# Klasmata.net
KiCad netlist of a schematic drawn in EAGLE
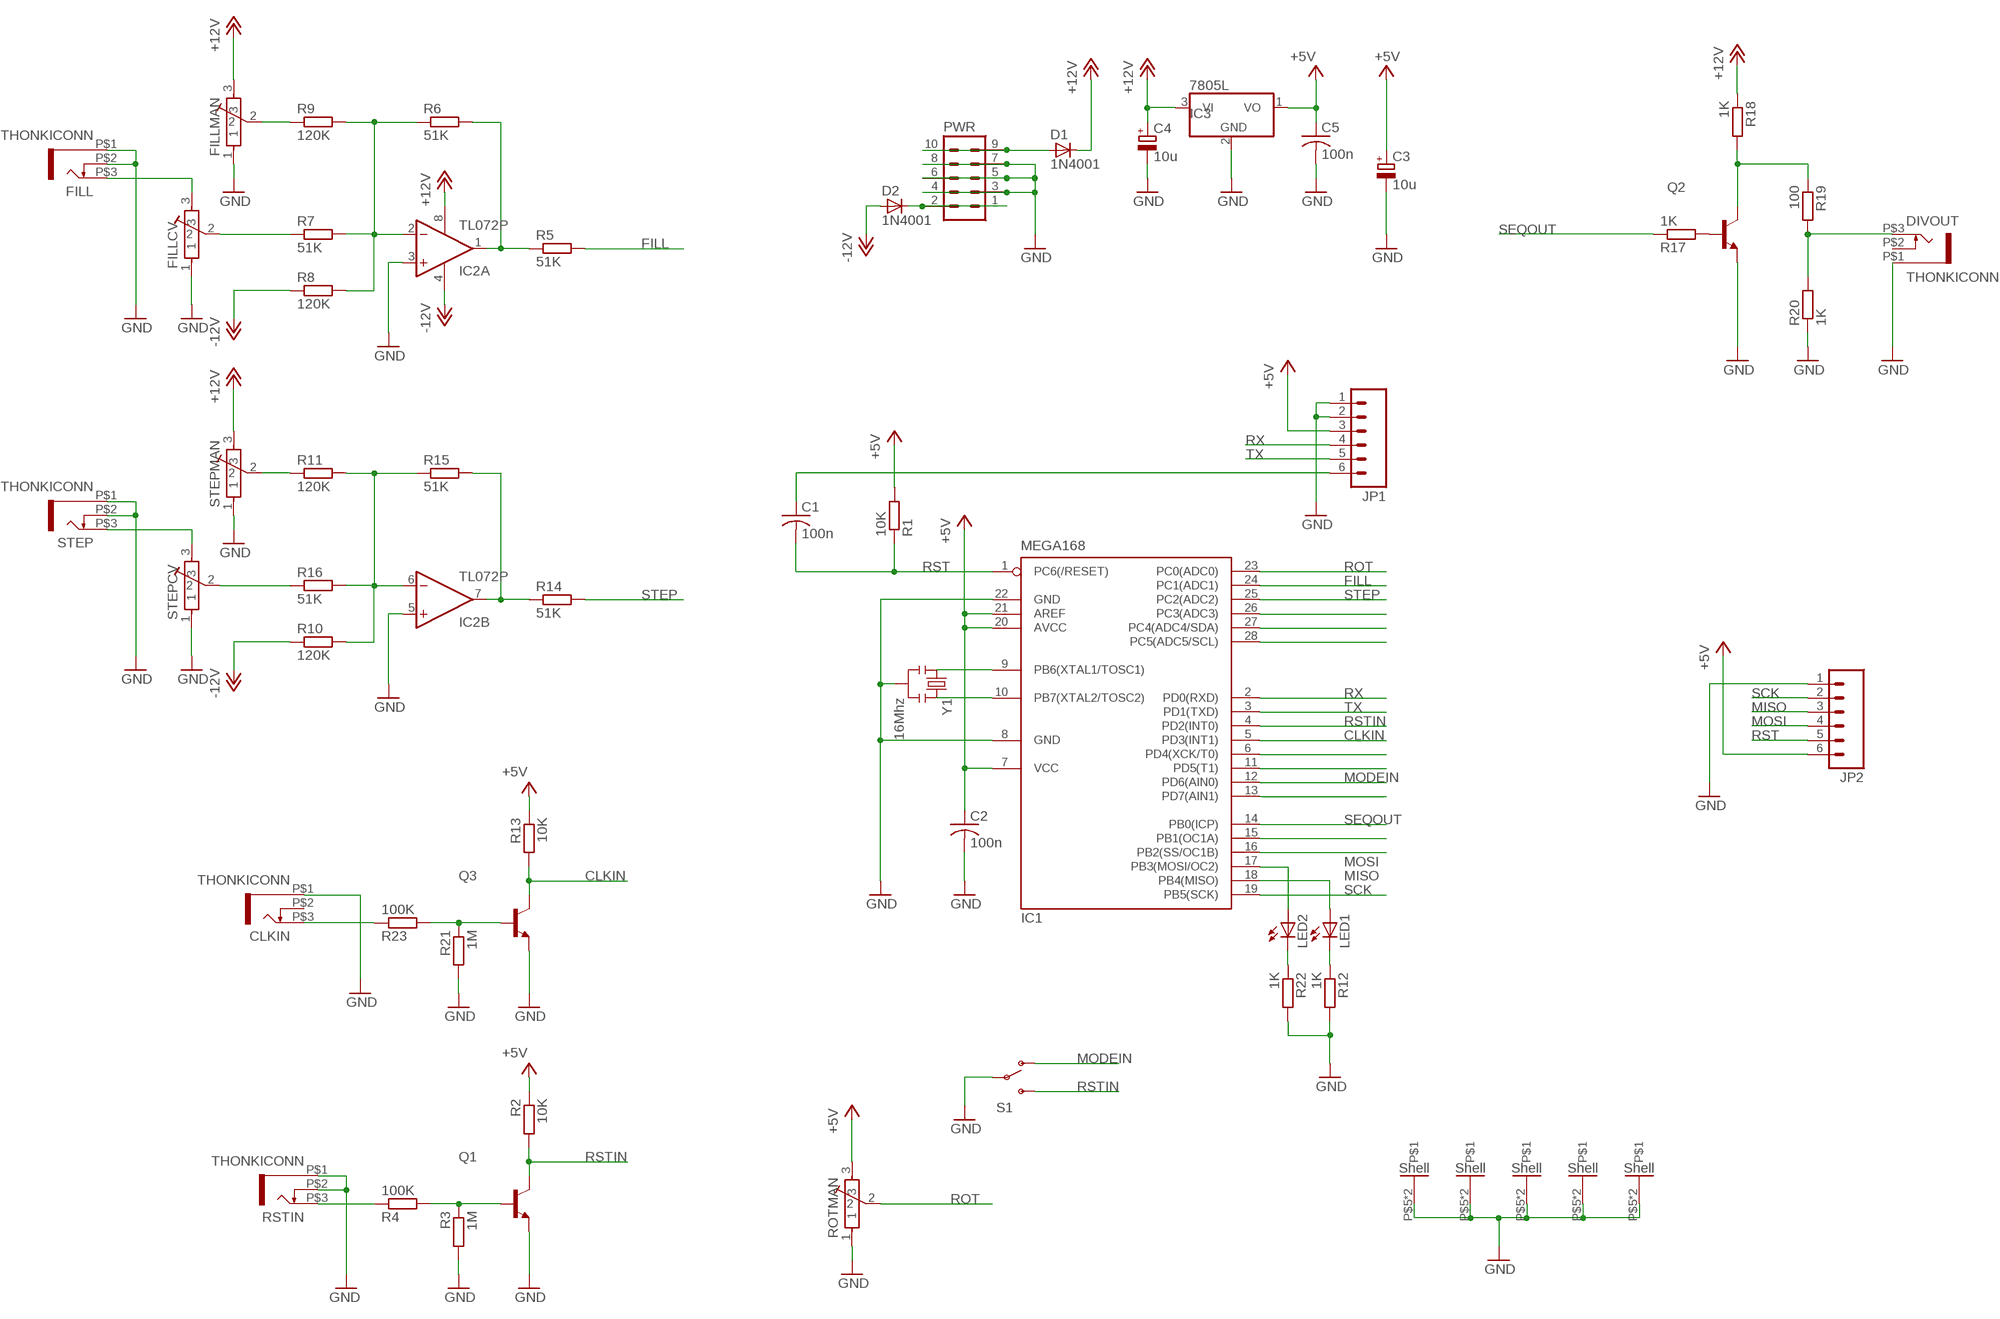
[diagram p0: schematic, sheet 1]

(export (version "E")
  (design (tool "Eeschema 10.0.6"))
  (components
    (comp (ref "C1")
      (value "100n")
      (footprint "eagle-import:C050-024X044")
      (libsource (lib "eagle-import") (part "C-US050-024X044"))
    )
    (comp (ref "C2")
      (value "100n")
      (footprint "eagle-import:C050-024X044")
      (libsource (lib "eagle-import") (part "C-US050-024X044"))
    )
    (comp (ref "C3")
      (value "10u")
      (footprint "eagle-import:E2,5-6")
      (libsource (lib "eagle-import") (part "resistor_CPOL-EUE2.5-6"))
    )
    (comp (ref "C4")
      (value "10u")
      (footprint "eagle-import:E5-6")
      (libsource (lib "eagle-import") (part "CPOL-EUE5-6"))
    )
    (comp (ref "C5")
      (value "100n")
      (footprint "eagle-import:C050-024X044")
      (libsource (lib "eagle-import") (part "C-US050-024X044"))
    )
    (comp (ref "CLKIN")
      (value "THONKICONN")
      (footprint "eagle-import:THONKICONN")
      (libsource (lib "eagle-import") (part "THONKICONN"))
    )
    (comp (ref "D1")
      (value "1N4001")
      (footprint "eagle-import:DIODE-1N4001")
      (libsource (lib "eagle-import") (part "DIODE1N4001"))
    )
    (comp (ref "D2")
      (value "1N4001")
      (footprint "eagle-import:DIODE-1N4001")
      (libsource (lib "eagle-import") (part "DIODE1N4001"))
    )
    (comp (ref "DIVOUT")
      (value "THONKICONN")
      (footprint "eagle-import:THONKICONN")
      (libsource (lib "eagle-import") (part "THONKICONN"))
    )
    (comp (ref "FILL")
      (value "THONKICONN")
      (footprint "eagle-import:THONKICONN")
      (libsource (lib "eagle-import") (part "THONKICONN"))
    )
    (comp (ref "FILLCV")
      (value "POT-ALPS-RK09L1140")
      (footprint "eagle-import:POT-ALPS-RK09L1140")
      (libsource (lib "eagle-import") (part "POT-ALPS-RK09L1140"))
    )
    (comp (ref "FILLMAN")
      (value "POT-ALPS-RK09L1140")
      (footprint "eagle-import:POT-ALPS-RK09L1140")
      (libsource (lib "eagle-import") (part "POT-ALPS-RK09L1140"))
    )
    (comp (ref "IC1")
      (value "MEGA168")
      (footprint "eagle-import:DIL28-3")
      (libsource (lib "eagle-import") (part "MEGA8-P"))
    )
    (comp (ref "IC2")
      (value "TL072P")
      (footprint "eagle-import:DIL08")
      (libsource (lib "eagle-import") (part "TL072P"))
    )
    (comp (ref "IC3")
      (value "7805L")
      (footprint "eagle-import:TO92")
      (libsource (lib "eagle-import") (part "78L05"))
    )
    (comp (ref "JP1")
      (value "M06SIP")
      (footprint "eagle-import:1X06")
      (libsource (lib "eagle-import") (part "M06SIP"))
    )
    (comp (ref "JP2")
      (value "M06SIP")
      (footprint "eagle-import:1X06")
      (libsource (lib "eagle-import") (part "M06SIP"))
    )
    (comp (ref "LED1")
      (value "LED3MM")
      (footprint "eagle-import:LED3MM")
      (libsource (lib "eagle-import") (part "LED3MM"))
    )
    (comp (ref "LED2")
      (value "LED3MM")
      (footprint "eagle-import:LED3MM")
      (libsource (lib "eagle-import") (part "LED3MM"))
    )
    (comp (ref "PWR")
      (value "MA05-2")
      (footprint "eagle-import:MA05-2")
      (libsource (lib "eagle-import") (part "MA05-2"))
    )
    (comp (ref "Q1")
      (value "2N3904-NPN-TO92-EBC")
      (footprint "eagle-import:TO92-EBC")
      (libsource (lib "eagle-import") (part "-NPN-TO92-EBC2N3904"))
    )
    (comp (ref "Q2")
      (value "2N3904-NPN-TO92-EBC")
      (footprint "eagle-import:TO92-EBC")
      (libsource (lib "eagle-import") (part "-NPN-TO92-EBC2N3904"))
    )
    (comp (ref "Q3")
      (value "2N3904-NPN-TO92-EBC")
      (footprint "eagle-import:TO92-EBC")
      (libsource (lib "eagle-import") (part "-NPN-TO92-EBC2N3904"))
    )
    (comp (ref "R1")
      (value "10K")
      (footprint "eagle-import:0204_7")
      (libsource (lib "eagle-import") (part "R-EU_0204/7"))
    )
    (comp (ref "R2")
      (value "10K")
      (footprint "eagle-import:0204_7")
      (libsource (lib "eagle-import") (part "R-EU_0204/7"))
    )
    (comp (ref "R3")
      (value "1M")
      (footprint "eagle-import:0204_7")
      (libsource (lib "eagle-import") (part "R-EU_0204/7"))
    )
    (comp (ref "R4")
      (value "100K")
      (footprint "eagle-import:0204_7")
      (libsource (lib "eagle-import") (part "R-EU_0204/7"))
    )
    (comp (ref "R5")
      (value "51K")
      (footprint "eagle-import:0204_7")
      (libsource (lib "eagle-import") (part "R-EU_0204/7"))
    )
    (comp (ref "R6")
      (value "51K")
      (footprint "eagle-import:0204_7")
      (libsource (lib "eagle-import") (part "R-EU_0204/7"))
    )
    (comp (ref "R7")
      (value "51K")
      (footprint "eagle-import:0204_7")
      (libsource (lib "eagle-import") (part "R-EU_0204/7"))
    )
    (comp (ref "R8")
      (value "120K")
      (footprint "eagle-import:0204_7")
      (libsource (lib "eagle-import") (part "R-EU_0204/7"))
    )
    (comp (ref "R9")
      (value "120K")
      (footprint "eagle-import:0204_7")
      (libsource (lib "eagle-import") (part "R-EU_0204/7"))
    )
    (comp (ref "R10")
      (value "120K")
      (footprint "eagle-import:0204_7")
      (libsource (lib "eagle-import") (part "R-EU_0204/7"))
    )
    (comp (ref "R11")
      (value "120K")
      (footprint "eagle-import:0204_7")
      (libsource (lib "eagle-import") (part "R-EU_0204/7"))
    )
    (comp (ref "R12")
      (value "1K")
      (footprint "eagle-import:0204_7")
      (libsource (lib "eagle-import") (part "R-EU_0204/7"))
    )
    (comp (ref "R13")
      (value "10K")
      (footprint "eagle-import:0204_7")
      (libsource (lib "eagle-import") (part "R-EU_0204/7"))
    )
    (comp (ref "R14")
      (value "51K")
      (footprint "eagle-import:0204_7")
      (libsource (lib "eagle-import") (part "R-EU_0204/7"))
    )
    (comp (ref "R15")
      (value "51K")
      (footprint "eagle-import:0204_7")
      (libsource (lib "eagle-import") (part "R-EU_0204/7"))
    )
    (comp (ref "R16")
      (value "51K")
      (footprint "eagle-import:0204_7")
      (libsource (lib "eagle-import") (part "R-EU_0204/7"))
    )
    (comp (ref "R17")
      (value "1K")
      (footprint "eagle-import:0204_7")
      (libsource (lib "eagle-import") (part "R-EU_0204/7"))
    )
    (comp (ref "R18")
      (value "1K")
      (footprint "eagle-import:0204_7")
      (libsource (lib "eagle-import") (part "R-EU_0204/7"))
    )
    (comp (ref "R19")
      (value "100")
      (footprint "eagle-import:0204_7")
      (libsource (lib "eagle-import") (part "R-EU_0204/7"))
    )
    (comp (ref "R20")
      (value "1K")
      (footprint "eagle-import:0204_7")
      (libsource (lib "eagle-import") (part "R-EU_0204/7"))
    )
    (comp (ref "R21")
      (value "1M")
      (footprint "eagle-import:0204_7")
      (libsource (lib "eagle-import") (part "R-EU_0204/7"))
    )
    (comp (ref "R22")
      (value "1K")
      (footprint "eagle-import:0204_7")
      (libsource (lib "eagle-import") (part "R-EU_0204/7"))
    )
    (comp (ref "R23")
      (value "100K")
      (footprint "eagle-import:0204_7")
      (libsource (lib "eagle-import") (part "R-EU_0204/7"))
    )
    (comp (ref "ROTMAN")
      (value "POT-ALPS-RK09L1140")
      (footprint "eagle-import:POT-ALPS-RK09L1140")
      (libsource (lib "eagle-import") (part "POT-ALPS-RK09L1140"))
    )
    (comp (ref "RSTIN")
      (value "THONKICONN")
      (footprint "eagle-import:THONKICONN")
      (libsource (lib "eagle-import") (part "THONKICONN"))
    )
    (comp (ref "S1")
      (value "SWITCH-SPST")
      (footprint "eagle-import:SWITCH-SPDT-SALECOM-T8014")
      (libsource (lib "eagle-import") (part "SWITCH-SPST"))
    )
    (comp (ref "STEP")
      (value "THONKICONN")
      (footprint "eagle-import:THONKICONN")
      (libsource (lib "eagle-import") (part "THONKICONN"))
    )
    (comp (ref "STEPCV")
      (value "POT-ALPS-RK09L1140")
      (footprint "eagle-import:POT-ALPS-RK09L1140")
      (libsource (lib "eagle-import") (part "POT-ALPS-RK09L1140"))
    )
    (comp (ref "STEPMAN")
      (value "POT-ALPS-RK09L1140")
      (footprint "eagle-import:POT-ALPS-RK09L1140")
      (libsource (lib "eagle-import") (part "POT-ALPS-RK09L1140"))
    )
    (comp (ref "Y1")
      (value "16Mhz")
      (footprint "eagle-import:RESONATOR-PTH")
      (libsource (lib "eagle-import") (part "RESONATORPTH"))
    )
  )
  (nets
    (net (code "1") (name "+5V") (class "Default")
      (node (ref "C2") (pin "1") (pinfunction "1_1") (pintype "passive"))
      (node (ref "C3") (pin "+") (pinfunction "+_+") (pintype "passive"))
      (node (ref "C5") (pin "1") (pinfunction "1_1") (pintype "passive"))
      (node (ref "IC1") (pin "20") (pinfunction "AVCC_20") (pintype "power_in"))
      (node (ref "IC1") (pin "21") (pinfunction "AREF_21") (pintype "passive"))
      (node (ref "IC1") (pin "7") (pinfunction "VCC_7") (pintype "power_in"))
      (node (ref "IC3") (pin "1") (pinfunction "VO_1") (pintype "passive"))
      (node (ref "JP1") (pin "3") (pinfunction "3_3") (pintype "passive"))
      (node (ref "JP2") (pin "6") (pinfunction "6_6") (pintype "passive"))
      (node (ref "R1") (pin "2") (pinfunction "2_2") (pintype "passive"))
      (node (ref "R13") (pin "1") (pinfunction "1_1") (pintype "passive"))
      (node (ref "R2") (pin "1") (pinfunction "1_1") (pintype "passive"))
      (node (ref "ROTMAN") (pin "3") (pinfunction "3_3") (pintype "bidirectional"))
    )
    (net (code "2") (name "+12V") (class "Default")
      (node (ref "C4") (pin "+") (pinfunction "+_+") (pintype "passive"))
      (node (ref "D1") (pin "C") (pinfunction "C_C") (pintype "passive"))
      (node (ref "FILLMAN") (pin "3") (pinfunction "3_3") (pintype "bidirectional"))
      (node (ref "IC2") (pin "8") (pinfunction "V+_8") (pintype "power_in"))
      (node (ref "IC3") (pin "3") (pinfunction "VI_3") (pintype "input"))
      (node (ref "R18") (pin "1") (pinfunction "1_1") (pintype "passive"))
      (node (ref "STEPMAN") (pin "3") (pinfunction "3_3") (pintype "bidirectional"))
    )
    (net (code "3") (name "-12V") (class "Default")
      (node (ref "D2") (pin "A") (pinfunction "A_A") (pintype "passive"))
      (node (ref "IC2") (pin "4") (pinfunction "V-_4") (pintype "power_in"))
      (node (ref "R10") (pin "1") (pinfunction "1_1") (pintype "passive"))
      (node (ref "R8") (pin "1") (pinfunction "1_1") (pintype "passive"))
    )
    (net (code "4") (name "/CLKIN") (class "Default")
      (node (ref "IC1") (pin "5") (pinfunction "PD3(INT1)_5") (pintype "bidirectional"))
      (node (ref "Q3") (pin "C") (pinfunction "C_C") (pintype "passive"))
      (node (ref "R13") (pin "2") (pinfunction "2_2") (pintype "passive"))
    )
    (net (code "5") (name "/FILL") (class "Default")
      (node (ref "IC1") (pin "24") (pinfunction "PC1(ADC1)_24") (pintype "bidirectional"))
      (node (ref "R5") (pin "2") (pinfunction "2_2") (pintype "passive"))
    )
    (net (code "6") (name "/MISO") (class "Default")
      (node (ref "IC1") (pin "18") (pinfunction "PB4(MISO)_18") (pintype "bidirectional"))
      (node (ref "JP2") (pin "3") (pinfunction "3_3") (pintype "passive"))
      (node (ref "LED1") (pin "A") (pinfunction "A_A") (pintype "passive"))
    )
    (net (code "7") (name "/MODEIN") (class "Default")
      (node (ref "IC1") (pin "12") (pinfunction "PD6(AIN0)_12") (pintype "bidirectional"))
      (node (ref "S1") (pin "1") (pinfunction "O_1") (pintype "passive"))
    )
    (net (code "8") (name "/MOSI") (class "Default")
      (node (ref "IC1") (pin "17") (pinfunction "PB3(MOSI/OC2)_17") (pintype "bidirectional"))
      (node (ref "JP2") (pin "4") (pinfunction "4_4") (pintype "passive"))
      (node (ref "LED2") (pin "A") (pinfunction "A_A") (pintype "passive"))
    )
    (net (code "9") (name "/ROT") (class "Default")
      (node (ref "IC1") (pin "23") (pinfunction "PC0(ADC0)_23") (pintype "bidirectional"))
      (node (ref "ROTMAN") (pin "2") (pinfunction "2_2") (pintype "bidirectional"))
    )
    (net (code "10") (name "/RST") (class "Default")
      (node (ref "C1") (pin "2") (pinfunction "2_2") (pintype "passive"))
      (node (ref "IC1") (pin "1") (pinfunction "PC6(/RESET)_1") (pintype "bidirectional"))
      (node (ref "JP2") (pin "5") (pinfunction "5_5") (pintype "passive"))
      (node (ref "R1") (pin "1") (pinfunction "1_1") (pintype "passive"))
    )
    (net (code "11") (name "/RSTIN") (class "Default")
      (node (ref "IC1") (pin "4") (pinfunction "PD2(INT0)_4") (pintype "bidirectional"))
      (node (ref "Q1") (pin "C") (pinfunction "C_C") (pintype "passive"))
      (node (ref "R2") (pin "2") (pinfunction "2_2") (pintype "passive"))
      (node (ref "S1") (pin "3") (pinfunction "S_3") (pintype "passive"))
    )
    (net (code "12") (name "/RX") (class "Default")
      (node (ref "IC1") (pin "2") (pinfunction "PD0(RXD)_2") (pintype "bidirectional"))
      (node (ref "JP1") (pin "4") (pinfunction "4_4") (pintype "passive"))
    )
    (net (code "13") (name "/SCK") (class "Default")
      (node (ref "IC1") (pin "19") (pinfunction "PB5(SCK)_19") (pintype "bidirectional"))
      (node (ref "JP2") (pin "2") (pinfunction "2_2") (pintype "passive"))
    )
    (net (code "14") (name "/SEQOUT") (class "Default")
      (node (ref "IC1") (pin "14") (pinfunction "PB0(ICP)_14") (pintype "bidirectional"))
      (node (ref "R17") (pin "1") (pinfunction "1_1") (pintype "passive"))
    )
    (net (code "15") (name "/STEP") (class "Default")
      (node (ref "IC1") (pin "25") (pinfunction "PC2(ADC2)_25") (pintype "bidirectional"))
      (node (ref "R14") (pin "2") (pinfunction "2_2") (pintype "passive"))
    )
    (net (code "16") (name "/TX") (class "Default")
      (node (ref "IC1") (pin "3") (pinfunction "PD1(TXD)_3") (pintype "bidirectional"))
      (node (ref "JP1") (pin "5") (pinfunction "5_5") (pintype "passive"))
    )
    (net (code "17") (name "GND") (class "Default")
      (node (ref "C2") (pin "2") (pinfunction "2_2") (pintype "passive"))
      (node (ref "C3") (pin "-") (pinfunction "-_-") (pintype "passive"))
      (node (ref "C4") (pin "-") (pinfunction "-_-") (pintype "passive"))
      (node (ref "C5") (pin "2") (pinfunction "2_2") (pintype "passive"))
      (node (ref "CLKIN") (pin "P$1") (pinfunction "5_P$1") (pintype "passive"))
      (node (ref "DIVOUT") (pin "P$1") (pinfunction "5_P$1") (pintype "passive"))
      (node (ref "FILL") (pin "P$1") (pinfunction "5_P$1") (pintype "passive"))
      (node (ref "FILL") (pin "P$2") (pinfunction "4_P$2") (pintype "passive"))
      (node (ref "FILLCV") (pin "1") (pinfunction "1_1") (pintype "bidirectional"))
      (node (ref "FILLCV") (pin "P$5") (pinfunction "P$1_P$5") (pintype "bidirectional"))
      (node (ref "FILLCV") (pin "P$6") (pinfunction "P$1_P$6") (pintype "bidirectional"))
      (node (ref "FILLMAN") (pin "1") (pinfunction "1_1") (pintype "bidirectional"))
      (node (ref "FILLMAN") (pin "P$5") (pinfunction "P$1_P$5") (pintype "bidirectional"))
      (node (ref "FILLMAN") (pin "P$6") (pinfunction "P$1_P$6") (pintype "bidirectional"))
      (node (ref "IC1") (pin "22") (pinfunction "GND_22") (pintype "power_in"))
      (node (ref "IC1") (pin "8") (pinfunction "GND_8") (pintype "power_in"))
      (node (ref "IC2") (pin "3") (pinfunction "+IN_3") (pintype "input"))
      (node (ref "IC2") (pin "5") (pinfunction "+IN_5") (pintype "input"))
      (node (ref "IC3") (pin "2") (pinfunction "GND_2") (pintype "passive"))
      (node (ref "JP1") (pin "1") (pinfunction "1_1") (pintype "passive"))
      (node (ref "JP1") (pin "2") (pinfunction "2_2") (pintype "passive"))
      (node (ref "JP2") (pin "1") (pinfunction "1_1") (pintype "passive"))
      (node (ref "PWR") (pin "3") (pinfunction "3_3") (pintype "passive"))
      (node (ref "PWR") (pin "4") (pinfunction "4_4") (pintype "passive"))
      (node (ref "PWR") (pin "5") (pinfunction "5_5") (pintype "passive"))
      (node (ref "PWR") (pin "6") (pinfunction "6_6") (pintype "passive"))
      (node (ref "PWR") (pin "7") (pinfunction "7_7") (pintype "passive"))
      (node (ref "PWR") (pin "8") (pinfunction "8_8") (pintype "passive"))
      (node (ref "Q1") (pin "E") (pinfunction "E_E") (pintype "passive"))
      (node (ref "Q2") (pin "E") (pinfunction "E_E") (pintype "passive"))
      (node (ref "Q3") (pin "E") (pinfunction "E_E") (pintype "passive"))
      (node (ref "R12") (pin "2") (pinfunction "2_2") (pintype "passive"))
      (node (ref "R20") (pin "1") (pinfunction "1_1") (pintype "passive"))
      (node (ref "R21") (pin "2") (pinfunction "2_2") (pintype "passive"))
      (node (ref "R22") (pin "2") (pinfunction "2_2") (pintype "passive"))
      (node (ref "R3") (pin "2") (pinfunction "2_2") (pintype "passive"))
      (node (ref "ROTMAN") (pin "1") (pinfunction "1_1") (pintype "bidirectional"))
      (node (ref "ROTMAN") (pin "P$5") (pinfunction "P$1_P$5") (pintype "bidirectional"))
      (node (ref "ROTMAN") (pin "P$6") (pinfunction "P$1_P$6") (pintype "bidirectional"))
      (node (ref "RSTIN") (pin "P$1") (pinfunction "5_P$1") (pintype "passive"))
      (node (ref "RSTIN") (pin "P$2") (pinfunction "4_P$2") (pintype "passive"))
      (node (ref "S1") (pin "2") (pinfunction "P_2") (pintype "passive"))
      (node (ref "STEP") (pin "P$1") (pinfunction "5_P$1") (pintype "passive"))
      (node (ref "STEP") (pin "P$2") (pinfunction "4_P$2") (pintype "passive"))
      (node (ref "STEPCV") (pin "1") (pinfunction "1_1") (pintype "bidirectional"))
      (node (ref "STEPCV") (pin "P$5") (pinfunction "P$1_P$5") (pintype "bidirectional"))
      (node (ref "STEPCV") (pin "P$6") (pinfunction "P$1_P$6") (pintype "bidirectional"))
      (node (ref "STEPMAN") (pin "1") (pinfunction "1_1") (pintype "bidirectional"))
      (node (ref "STEPMAN") (pin "P$5") (pinfunction "P$1_P$5") (pintype "bidirectional"))
      (node (ref "STEPMAN") (pin "P$6") (pinfunction "P$1_P$6") (pintype "bidirectional"))
      (node (ref "Y1") (pin "2") (pinfunction "2_2") (pintype "passive"))
    )
    (net (code "18") (name "Net-(C1-Pad1)") (class "Default")
      (node (ref "C1") (pin "1") (pinfunction "1_1") (pintype "passive"))
      (node (ref "JP1") (pin "6") (pinfunction "6_6") (pintype "passive"))
    )
    (net (code "19") (name "Net-(CLKIN-3)") (class "Default")
      (node (ref "CLKIN") (pin "P$3") (pinfunction "3_P$3") (pintype "passive"))
      (node (ref "R23") (pin "1") (pinfunction "1_1") (pintype "passive"))
    )
    (net (code "20") (name "Net-(D1-PadA)") (class "Default")
      (node (ref "D1") (pin "A") (pinfunction "A_A") (pintype "passive"))
      (node (ref "PWR") (pin "10") (pinfunction "10_10") (pintype "passive"))
      (node (ref "PWR") (pin "9") (pinfunction "9_9") (pintype "passive"))
    )
    (net (code "21") (name "Net-(D2-PadC)") (class "Default")
      (node (ref "D2") (pin "C") (pinfunction "C_C") (pintype "passive"))
      (node (ref "PWR") (pin "1") (pinfunction "1_1") (pintype "passive"))
      (node (ref "PWR") (pin "2") (pinfunction "2_2") (pintype "passive"))
    )
    (net (code "22") (name "Net-(DIVOUT-3)") (class "Default")
      (node (ref "DIVOUT") (pin "P$3") (pinfunction "3_P$3") (pintype "passive"))
      (node (ref "R19") (pin "2") (pinfunction "2_2") (pintype "passive"))
      (node (ref "R20") (pin "2") (pinfunction "2_2") (pintype "passive"))
    )
    (net (code "23") (name "Net-(FILL-3)") (class "Default")
      (node (ref "FILL") (pin "P$3") (pinfunction "3_P$3") (pintype "passive"))
      (node (ref "FILLCV") (pin "3") (pinfunction "3_3") (pintype "bidirectional"))
    )
    (net (code "24") (name "Net-(FILLCV-Pad2)") (class "Default")
      (node (ref "FILLCV") (pin "2") (pinfunction "2_2") (pintype "bidirectional"))
      (node (ref "R7") (pin "1") (pinfunction "1_1") (pintype "passive"))
    )
    (net (code "25") (name "Net-(FILLMAN-Pad2)") (class "Default")
      (node (ref "FILLMAN") (pin "2") (pinfunction "2_2") (pintype "bidirectional"))
      (node (ref "R9") (pin "1") (pinfunction "1_1") (pintype "passive"))
    )
    (net (code "26") (name "Net-(IC1-PB6(XTAL1{slash}TOSC1))") (class "Default")
      (node (ref "IC1") (pin "9") (pinfunction "PB6(XTAL1/TOSC1)_9") (pintype "bidirectional"))
      (node (ref "Y1") (pin "1") (pinfunction "1_1") (pintype "passive"))
    )
    (net (code "27") (name "Net-(IC1-PB7(XTAL2{slash}TOSC2))") (class "Default")
      (node (ref "IC1") (pin "10") (pinfunction "PB7(XTAL2/TOSC2)_10") (pintype "bidirectional"))
      (node (ref "Y1") (pin "3") (pinfunction "3_3") (pintype "passive"))
    )
    (net (code "28") (name "Net-(IC2A--IN)") (class "Default")
      (node (ref "IC2") (pin "2") (pinfunction "-IN_2") (pintype "input"))
      (node (ref "R6") (pin "1") (pinfunction "1_1") (pintype "passive"))
      (node (ref "R7") (pin "2") (pinfunction "2_2") (pintype "passive"))
      (node (ref "R8") (pin "2") (pinfunction "2_2") (pintype "passive"))
      (node (ref "R9") (pin "2") (pinfunction "2_2") (pintype "passive"))
    )
    (net (code "29") (name "Net-(IC2A-OUT)") (class "Default")
      (node (ref "IC2") (pin "1") (pinfunction "OUT_1") (pintype "output"))
      (node (ref "R5") (pin "1") (pinfunction "1_1") (pintype "passive"))
      (node (ref "R6") (pin "2") (pinfunction "2_2") (pintype "passive"))
    )
    (net (code "30") (name "Net-(IC2B--IN)") (class "Default")
      (node (ref "IC2") (pin "6") (pinfunction "-IN_6") (pintype "input"))
      (node (ref "R10") (pin "2") (pinfunction "2_2") (pintype "passive"))
      (node (ref "R11") (pin "2") (pinfunction "2_2") (pintype "passive"))
      (node (ref "R15") (pin "1") (pinfunction "1_1") (pintype "passive"))
      (node (ref "R16") (pin "2") (pinfunction "2_2") (pintype "passive"))
    )
    (net (code "31") (name "Net-(IC2B-OUT)") (class "Default")
      (node (ref "IC2") (pin "7") (pinfunction "OUT_7") (pintype "output"))
      (node (ref "R14") (pin "1") (pinfunction "1_1") (pintype "passive"))
      (node (ref "R15") (pin "2") (pinfunction "2_2") (pintype "passive"))
    )
    (net (code "32") (name "Net-(LED1-C)") (class "Default")
      (node (ref "LED1") (pin "K") (pinfunction "C_K") (pintype "passive"))
      (node (ref "R12") (pin "1") (pinfunction "1_1") (pintype "passive"))
    )
    (net (code "33") (name "Net-(LED2-C)") (class "Default")
      (node (ref "LED2") (pin "K") (pinfunction "C_K") (pintype "passive"))
      (node (ref "R22") (pin "1") (pinfunction "1_1") (pintype "passive"))
    )
    (net (code "34") (name "Net-(Q1-PadB)") (class "Default")
      (node (ref "Q1") (pin "B") (pinfunction "B_B") (pintype "passive"))
      (node (ref "R3") (pin "1") (pinfunction "1_1") (pintype "passive"))
      (node (ref "R4") (pin "2") (pinfunction "2_2") (pintype "passive"))
    )
    (net (code "35") (name "Net-(Q2-PadB)") (class "Default")
      (node (ref "Q2") (pin "B") (pinfunction "B_B") (pintype "passive"))
      (node (ref "R17") (pin "2") (pinfunction "2_2") (pintype "passive"))
    )
    (net (code "36") (name "Net-(Q2-PadC)") (class "Default")
      (node (ref "Q2") (pin "C") (pinfunction "C_C") (pintype "passive"))
      (node (ref "R18") (pin "2") (pinfunction "2_2") (pintype "passive"))
      (node (ref "R19") (pin "1") (pinfunction "1_1") (pintype "passive"))
    )
    (net (code "37") (name "Net-(Q3-PadB)") (class "Default")
      (node (ref "Q3") (pin "B") (pinfunction "B_B") (pintype "passive"))
      (node (ref "R21") (pin "1") (pinfunction "1_1") (pintype "passive"))
      (node (ref "R23") (pin "2") (pinfunction "2_2") (pintype "passive"))
    )
    (net (code "38") (name "Net-(R11-Pad1)") (class "Default")
      (node (ref "R11") (pin "1") (pinfunction "1_1") (pintype "passive"))
      (node (ref "STEPMAN") (pin "2") (pinfunction "2_2") (pintype "bidirectional"))
    )
    (net (code "39") (name "Net-(R16-Pad1)") (class "Default")
      (node (ref "R16") (pin "1") (pinfunction "1_1") (pintype "passive"))
      (node (ref "STEPCV") (pin "2") (pinfunction "2_2") (pintype "bidirectional"))
    )
    (net (code "40") (name "Net-(RSTIN-3)") (class "Default")
      (node (ref "R4") (pin "1") (pinfunction "1_1") (pintype "passive"))
      (node (ref "RSTIN") (pin "P$3") (pinfunction "3_P$3") (pintype "passive"))
    )
    (net (code "41") (name "Net-(STEP-3)") (class "Default")
      (node (ref "STEP") (pin "P$3") (pinfunction "3_P$3") (pintype "passive"))
      (node (ref "STEPCV") (pin "3") (pinfunction "3_3") (pintype "bidirectional"))
    )
    (net (code "42") (name "unconnected-(CLKIN-4-PadP$2)") (class "Default")
      (node (ref "CLKIN") (pin "P$2") (pinfunction "4_P$2") (pintype "passive"))
    )
    (net (code "43") (name "unconnected-(DIVOUT-4-PadP$2)") (class "Default")
      (node (ref "DIVOUT") (pin "P$2") (pinfunction "4_P$2") (pintype "passive"))
    )
    (net (code "44") (name "unconnected-(IC1-PB1(OC1A)-Pad15)") (class "Default")
      (node (ref "IC1") (pin "15") (pinfunction "PB1(OC1A)_15") (pintype "bidirectional"))
    )
    (net (code "45") (name "unconnected-(IC1-PB2(SS{slash}OC1B)-Pad16)") (class "Default")
      (node (ref "IC1") (pin "16") (pinfunction "PB2(SS/OC1B)_16") (pintype "bidirectional"))
    )
    (net (code "46") (name "unconnected-(IC1-PC3(ADC3)-Pad26)") (class "Default")
      (node (ref "IC1") (pin "26") (pinfunction "PC3(ADC3)_26") (pintype "bidirectional"))
    )
    (net (code "47") (name "unconnected-(IC1-PC4(ADC4{slash}SDA)-Pad27)") (class "Default")
      (node (ref "IC1") (pin "27") (pinfunction "PC4(ADC4/SDA)_27") (pintype "bidirectional"))
    )
    (net (code "48") (name "unconnected-(IC1-PC5(ADC5{slash}SCL)-Pad28)") (class "Default")
      (node (ref "IC1") (pin "28") (pinfunction "PC5(ADC5/SCL)_28") (pintype "bidirectional"))
    )
    (net (code "49") (name "unconnected-(IC1-PD4(XCK{slash}T0)-Pad6)") (class "Default")
      (node (ref "IC1") (pin "6") (pinfunction "PD4(XCK/T0)_6") (pintype "bidirectional"))
    )
    (net (code "50") (name "unconnected-(IC1-PD5(T1)-Pad11)") (class "Default")
      (node (ref "IC1") (pin "11") (pinfunction "PD5(T1)_11") (pintype "bidirectional"))
    )
    (net (code "51") (name "unconnected-(IC1-PD7(AIN1)-Pad13)") (class "Default")
      (node (ref "IC1") (pin "13") (pinfunction "PD7(AIN1)_13") (pintype "bidirectional"))
    )
  )
)
